# Power_Distro_PCB.net
KiCad netlist of a schematic drawn in EAGLE
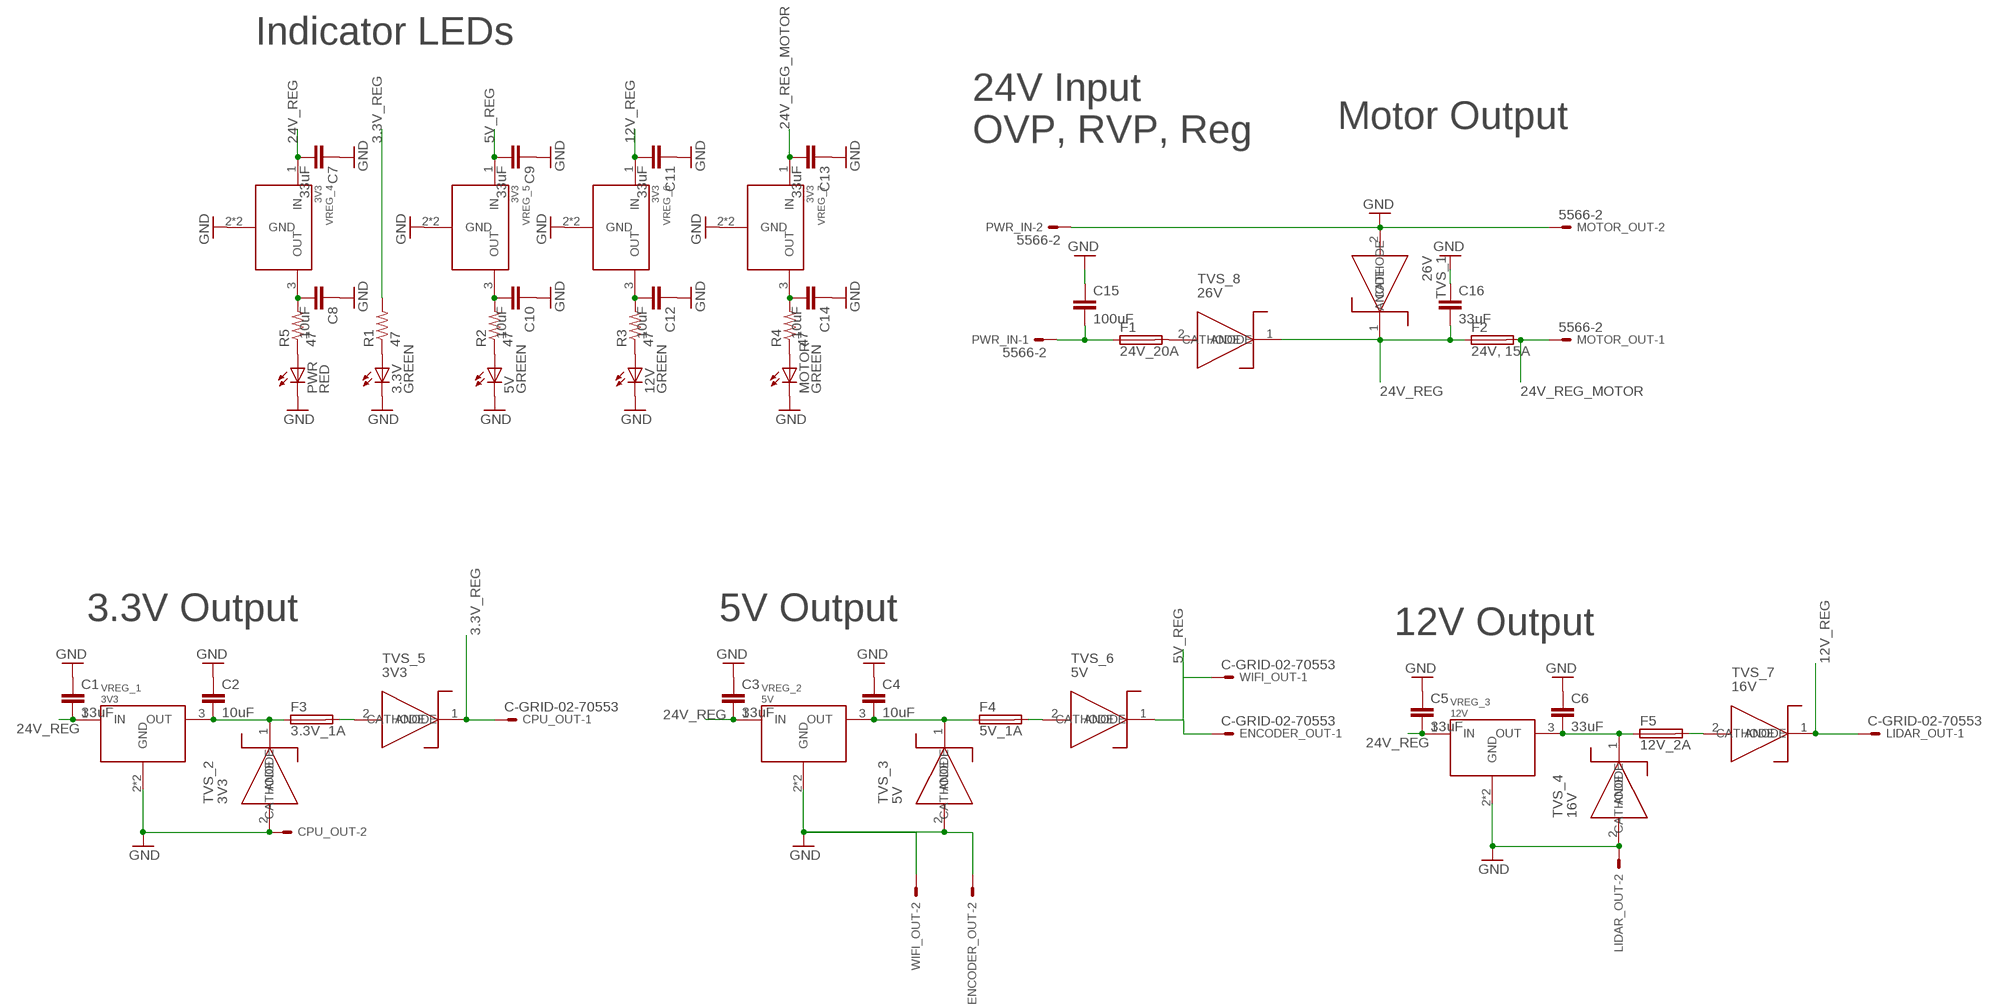
[diagram p0: schematic, sheet 1]

(export (version "E")
  (design (tool "Eeschema 10.0.6"))
  (components
    (comp (ref "3.3V")
      (value "GREEN")
      (footprint "eagle-import:SML1206")
      (libsource (lib "eagle-import") (part "LEDSML1206"))
    )
    (comp (ref "5V")
      (value "GREEN")
      (footprint "eagle-import:SML1206")
      (libsource (lib "eagle-import") (part "LEDSML1206"))
    )
    (comp (ref "12V")
      (value "GREEN")
      (footprint "eagle-import:SML1206")
      (libsource (lib "eagle-import") (part "LEDSML1206"))
    )
    (comp (ref "C1")
      (value "33uF")
      (footprint "eagle-import:C1206")
      (libsource (lib "eagle-import") (part "C-EUC1206"))
    )
    (comp (ref "C2")
      (value "10uF")
      (footprint "eagle-import:C1206")
      (libsource (lib "eagle-import") (part "C-EUC1206"))
    )
    (comp (ref "C3")
      (value "33uF")
      (footprint "eagle-import:C1206")
      (libsource (lib "eagle-import") (part "C-EUC1206"))
    )
    (comp (ref "C4")
      (value "10uF")
      (footprint "eagle-import:C1206")
      (libsource (lib "eagle-import") (part "C-EUC1206"))
    )
    (comp (ref "C5")
      (value "33uF")
      (footprint "eagle-import:C1206")
      (libsource (lib "eagle-import") (part "C-EUC1206"))
    )
    (comp (ref "C6")
      (value "33uF")
      (footprint "eagle-import:C1206")
      (libsource (lib "eagle-import") (part "C-EUC1206"))
    )
    (comp (ref "C7")
      (value "33uF")
      (footprint "eagle-import:C1206")
      (libsource (lib "eagle-import") (part "C-EUC1206"))
    )
    (comp (ref "C8")
      (value "10uF")
      (footprint "eagle-import:C1206")
      (libsource (lib "eagle-import") (part "C-EUC1206"))
    )
    (comp (ref "C9")
      (value "33uF")
      (footprint "eagle-import:C1206")
      (libsource (lib "eagle-import") (part "C-EUC1206"))
    )
    (comp (ref "C10")
      (value "10uF")
      (footprint "eagle-import:C1206")
      (libsource (lib "eagle-import") (part "C-EUC1206"))
    )
    (comp (ref "C11")
      (value "33uF")
      (footprint "eagle-import:C1206")
      (libsource (lib "eagle-import") (part "C-EUC1206"))
    )
    (comp (ref "C12")
      (value "10uF")
      (footprint "eagle-import:C1206")
      (libsource (lib "eagle-import") (part "C-EUC1206"))
    )
    (comp (ref "C13")
      (value "33uF")
      (footprint "eagle-import:C1206")
      (libsource (lib "eagle-import") (part "C-EUC1206"))
    )
    (comp (ref "C14")
      (value "10uF")
      (footprint "eagle-import:C1206")
      (libsource (lib "eagle-import") (part "C-EUC1206"))
    )
    (comp (ref "C15")
      (value "100uF")
      (footprint "eagle-import:C1206")
      (libsource (lib "eagle-import") (part "C-EUC1206"))
    )
    (comp (ref "C16")
      (value "33uF")
      (footprint "eagle-import:C1206")
      (libsource (lib "eagle-import") (part "C-EUC1206"))
    )
    (comp (ref "CPU_OUT")
      (value "C-GRID-02-70553")
      (footprint "eagle-import:70553-02")
      (libsource (lib "eagle-import") (part "C-GRID-02-70553"))
    )
    (comp (ref "ENCODER_OUT")
      (value "C-GRID-02-70553")
      (footprint "eagle-import:70553-02")
      (libsource (lib "eagle-import") (part "C-GRID-02-70553"))
    )
    (comp (ref "F1")
      (value "24V_20A")
      (footprint "eagle-import:TE5")
      (libsource (lib "eagle-import") (part "TE5"))
    )
    (comp (ref "F2")
      (value "24V, 15A")
      (footprint "eagle-import:TE5")
      (libsource (lib "eagle-import") (part "TE5"))
    )
    (comp (ref "F3")
      (value "3.3V_1A")
      (footprint "eagle-import:TE5")
      (libsource (lib "eagle-import") (part "TE5"))
    )
    (comp (ref "F4")
      (value "5V_1A")
      (footprint "eagle-import:TE5")
      (libsource (lib "eagle-import") (part "TE5"))
    )
    (comp (ref "F5")
      (value "12V_2A")
      (footprint "eagle-import:TE5")
      (libsource (lib "eagle-import") (part "TE5"))
    )
    (comp (ref "LIDAR_OUT")
      (value "C-GRID-02-70553")
      (footprint "eagle-import:70553-02")
      (libsource (lib "eagle-import") (part "C-GRID-02-70553"))
    )
    (comp (ref "MOTOR")
      (value "GREEN")
      (footprint "eagle-import:SML1206")
      (libsource (lib "eagle-import") (part "LEDSML1206"))
    )
    (comp (ref "MOTOR_OUT")
      (value "5566-2")
      (footprint "eagle-import:5566-2")
      (libsource (lib "eagle-import") (part "5566-2"))
    )
    (comp (ref "PWR")
      (value "RED")
      (footprint "eagle-import:SML1206")
      (libsource (lib "eagle-import") (part "LEDSML1206"))
    )
    (comp (ref "PWR_IN")
      (value "5566-2")
      (footprint "eagle-import:5566-2")
      (libsource (lib "eagle-import") (part "5566-2"))
    )
    (comp (ref "R1")
      (value "47")
      (footprint "eagle-import:R1206")
      (libsource (lib "eagle-import") (part "R-US_R1206"))
    )
    (comp (ref "R2")
      (value "47")
      (footprint "eagle-import:R1206")
      (libsource (lib "eagle-import") (part "R-US_R1206"))
    )
    (comp (ref "R3")
      (value "47")
      (footprint "eagle-import:R1206")
      (libsource (lib "eagle-import") (part "R-US_R1206"))
    )
    (comp (ref "R4")
      (value "47")
      (footprint "eagle-import:R1206")
      (libsource (lib "eagle-import") (part "R-US_R1206"))
    )
    (comp (ref "R5")
      (value "47")
      (footprint "eagle-import:R1206")
      (libsource (lib "eagle-import") (part "R-US_R1206"))
    )
    (comp (ref "TVS_1")
      (value "26V")
      (footprint "eagle-import:DO-214AC")
      (libsource (lib "eagle-import") (part "SMAJ26A_TVSSMA"))
    )
    (comp (ref "TVS_2")
      (value "3V3")
      (footprint "eagle-import:DO-214AA")
      (libsource (lib "eagle-import") (part "SMBJ3V3_TVSSMB"))
    )
    (comp (ref "TVS_3")
      (value "5V")
      (footprint "eagle-import:DO-214AC")
      (libsource (lib "eagle-import") (part "SMAJ5.0_TVSSMA"))
    )
    (comp (ref "TVS_4")
      (value "16V")
      (footprint "eagle-import:DO-214AC")
      (libsource (lib "eagle-import") (part "PRSMA16_TVS"))
    )
    (comp (ref "TVS_5")
      (value "3V3")
      (footprint "eagle-import:DO-214AA")
      (libsource (lib "eagle-import") (part "SMBJ3V3_TVSSMB"))
    )
    (comp (ref "TVS_6")
      (value "5V")
      (footprint "eagle-import:DO-214AC")
      (libsource (lib "eagle-import") (part "SMAJ5.0_TVSSMA"))
    )
    (comp (ref "TVS_7")
      (value "16V")
      (footprint "eagle-import:DO-214AC")
      (libsource (lib "eagle-import") (part "PRSMA16_TVS"))
    )
    (comp (ref "TVS_8")
      (value "26V")
      (footprint "eagle-import:DO-214AC")
      (libsource (lib "eagle-import") (part "SMAJ26A_TVSSMA"))
    )
    (comp (ref "VREG_1")
      (value "3V3")
      (footprint "eagle-import:TO-263-3")
      (libsource (lib "eagle-import") (part "HIGH-CURRENT_REGSMA"))
    )
    (comp (ref "VREG_2")
      (value "5V")
      (footprint "eagle-import:TO-263-3")
      (libsource (lib "eagle-import") (part "HIGH-CURRENT_REGSMA"))
    )
    (comp (ref "VREG_3")
      (value "12V")
      (footprint "eagle-import:TO-263-3")
      (libsource (lib "eagle-import") (part "HIGH-CURRENT_REGSMA"))
    )
    (comp (ref "VREG_4")
      (value "3V3")
      (footprint "eagle-import:TO-263-3")
      (libsource (lib "eagle-import") (part "HIGH-CURRENT_REGSMA"))
    )
    (comp (ref "VREG_5")
      (value "3V3")
      (footprint "eagle-import:TO-263-3")
      (libsource (lib "eagle-import") (part "HIGH-CURRENT_REGSMA"))
    )
    (comp (ref "VREG_6")
      (value "3V3")
      (footprint "eagle-import:TO-263-3")
      (libsource (lib "eagle-import") (part "HIGH-CURRENT_REGSMA"))
    )
    (comp (ref "VREG_7")
      (value "3V3")
      (footprint "eagle-import:TO-263-3")
      (libsource (lib "eagle-import") (part "HIGH-CURRENT_REGSMA"))
    )
    (comp (ref "WIFI_OUT")
      (value "C-GRID-02-70553")
      (footprint "eagle-import:70553-02")
      (libsource (lib "eagle-import") (part "C-GRID-02-70553"))
    )
  )
  (nets
    (net (code "1") (name "/3.3V_REG") (class "Default")
      (node (ref "CPU_OUT") (pin "1") (pinfunction "S_1") (pintype "passive"))
      (node (ref "R1") (pin "2") (pinfunction "2_2") (pintype "passive"))
      (node (ref "TVS_5") (pin "1") (pinfunction "CATHODE_1") (pintype "bidirectional"))
    )
    (net (code "2") (name "/5V_REG") (class "Default")
      (node (ref "C9") (pin "2") (pinfunction "2_2") (pintype "passive"))
      (node (ref "ENCODER_OUT") (pin "1") (pinfunction "S_1") (pintype "passive"))
      (node (ref "TVS_6") (pin "1") (pinfunction "CATHODE_1") (pintype "bidirectional"))
      (node (ref "VREG_5") (pin "1") (pinfunction "IN_1") (pintype "bidirectional"))
      (node (ref "WIFI_OUT") (pin "1") (pinfunction "S_1") (pintype "passive"))
    )
    (net (code "3") (name "/12V_REG") (class "Default")
      (node (ref "C11") (pin "2") (pinfunction "2_2") (pintype "passive"))
      (node (ref "LIDAR_OUT") (pin "1") (pinfunction "S_1") (pintype "passive"))
      (node (ref "TVS_7") (pin "1") (pinfunction "CATHODE_1") (pintype "bidirectional"))
      (node (ref "VREG_6") (pin "1") (pinfunction "IN_1") (pintype "bidirectional"))
    )
    (net (code "4") (name "/24V_REG") (class "Default")
      (node (ref "C1") (pin "2") (pinfunction "2_2") (pintype "passive"))
      (node (ref "C16") (pin "2") (pinfunction "2_2") (pintype "passive"))
      (node (ref "C3") (pin "2") (pinfunction "2_2") (pintype "passive"))
      (node (ref "C5") (pin "2") (pinfunction "2_2") (pintype "passive"))
      (node (ref "C7") (pin "2") (pinfunction "2_2") (pintype "passive"))
      (node (ref "F2") (pin "1") (pinfunction "1_1") (pintype "passive"))
      (node (ref "TVS_1") (pin "1") (pinfunction "CATHODE_1") (pintype "bidirectional"))
      (node (ref "TVS_8") (pin "1") (pinfunction "CATHODE_1") (pintype "bidirectional"))
      (node (ref "VREG_1") (pin "1") (pinfunction "IN_1") (pintype "bidirectional"))
      (node (ref "VREG_2") (pin "1") (pinfunction "IN_1") (pintype "bidirectional"))
      (node (ref "VREG_3") (pin "1") (pinfunction "IN_1") (pintype "bidirectional"))
      (node (ref "VREG_4") (pin "1") (pinfunction "IN_1") (pintype "bidirectional"))
    )
    (net (code "5") (name "/24V_REG_MOTOR") (class "Default")
      (node (ref "C13") (pin "2") (pinfunction "2_2") (pintype "passive"))
      (node (ref "F2") (pin "2") (pinfunction "2_2") (pintype "passive"))
      (node (ref "MOTOR_OUT") (pin "1") (pinfunction "S_1") (pintype "passive"))
      (node (ref "VREG_7") (pin "1") (pinfunction "IN_1") (pintype "bidirectional"))
    )
    (net (code "6") (name "GND") (class "Default")
      (node (ref "12V") (pin "C") (pinfunction "C_C") (pintype "passive"))
      (node (ref "3.3V") (pin "C") (pinfunction "C_C") (pintype "passive"))
      (node (ref "5V") (pin "C") (pinfunction "C_C") (pintype "passive"))
      (node (ref "C1") (pin "1") (pinfunction "1_1") (pintype "passive"))
      (node (ref "C10") (pin "1") (pinfunction "1_1") (pintype "passive"))
      (node (ref "C11") (pin "1") (pinfunction "1_1") (pintype "passive"))
      (node (ref "C12") (pin "1") (pinfunction "1_1") (pintype "passive"))
      (node (ref "C13") (pin "1") (pinfunction "1_1") (pintype "passive"))
      (node (ref "C14") (pin "1") (pinfunction "1_1") (pintype "passive"))
      (node (ref "C15") (pin "1") (pinfunction "1_1") (pintype "passive"))
      (node (ref "C16") (pin "1") (pinfunction "1_1") (pintype "passive"))
      (node (ref "C2") (pin "1") (pinfunction "1_1") (pintype "passive"))
      (node (ref "C3") (pin "1") (pinfunction "1_1") (pintype "passive"))
      (node (ref "C4") (pin "1") (pinfunction "1_1") (pintype "passive"))
      (node (ref "C5") (pin "1") (pinfunction "1_1") (pintype "passive"))
      (node (ref "C6") (pin "1") (pinfunction "1_1") (pintype "passive"))
      (node (ref "C7") (pin "1") (pinfunction "1_1") (pintype "passive"))
      (node (ref "C8") (pin "1") (pinfunction "1_1") (pintype "passive"))
      (node (ref "C9") (pin "1") (pinfunction "1_1") (pintype "passive"))
      (node (ref "CPU_OUT") (pin "2") (pinfunction "S_2") (pintype "passive"))
      (node (ref "ENCODER_OUT") (pin "2") (pinfunction "S_2") (pintype "passive"))
      (node (ref "LIDAR_OUT") (pin "2") (pinfunction "S_2") (pintype "passive"))
      (node (ref "MOTOR") (pin "C") (pinfunction "C_C") (pintype "passive"))
      (node (ref "MOTOR_OUT") (pin "2") (pinfunction "S_2") (pintype "passive"))
      (node (ref "PWR") (pin "C") (pinfunction "C_C") (pintype "passive"))
      (node (ref "PWR_IN") (pin "2") (pinfunction "S_2") (pintype "passive"))
      (node (ref "TVS_1") (pin "2") (pinfunction "ANODE_2") (pintype "bidirectional"))
      (node (ref "TVS_2") (pin "2") (pinfunction "ANODE_2") (pintype "bidirectional"))
      (node (ref "TVS_3") (pin "2") (pinfunction "ANODE_2") (pintype "bidirectional"))
      (node (ref "TVS_4") (pin "2") (pinfunction "ANODE_2") (pintype "bidirectional"))
      (node (ref "VREG_1") (pin "2") (pinfunction "GND_2") (pintype "bidirectional"))
      (node (ref "VREG_1") (pin "4") (pinfunction "GND_4") (pintype "bidirectional"))
      (node (ref "VREG_2") (pin "2") (pinfunction "GND_2") (pintype "bidirectional"))
      (node (ref "VREG_2") (pin "4") (pinfunction "GND_4") (pintype "bidirectional"))
      (node (ref "VREG_3") (pin "2") (pinfunction "GND_2") (pintype "bidirectional"))
      (node (ref "VREG_3") (pin "4") (pinfunction "GND_4") (pintype "bidirectional"))
      (node (ref "VREG_4") (pin "2") (pinfunction "GND_2") (pintype "bidirectional"))
      (node (ref "VREG_4") (pin "4") (pinfunction "GND_4") (pintype "bidirectional"))
      (node (ref "VREG_5") (pin "2") (pinfunction "GND_2") (pintype "bidirectional"))
      (node (ref "VREG_5") (pin "4") (pinfunction "GND_4") (pintype "bidirectional"))
      (node (ref "VREG_6") (pin "2") (pinfunction "GND_2") (pintype "bidirectional"))
      (node (ref "VREG_6") (pin "4") (pinfunction "GND_4") (pintype "bidirectional"))
      (node (ref "VREG_7") (pin "2") (pinfunction "GND_2") (pintype "bidirectional"))
      (node (ref "VREG_7") (pin "4") (pinfunction "GND_4") (pintype "bidirectional"))
      (node (ref "WIFI_OUT") (pin "2") (pinfunction "S_2") (pintype "passive"))
    )
    (net (code "7") (name "Net-(3.3V-PadA)") (class "Default")
      (node (ref "3.3V") (pin "A") (pinfunction "A_A") (pintype "passive"))
      (node (ref "R1") (pin "1") (pinfunction "1_1") (pintype "passive"))
    )
    (net (code "8") (name "Net-(5V-PadA)") (class "Default")
      (node (ref "5V") (pin "A") (pinfunction "A_A") (pintype "passive"))
      (node (ref "R2") (pin "1") (pinfunction "1_1") (pintype "passive"))
    )
    (net (code "9") (name "Net-(12V-PadA)") (class "Default")
      (node (ref "12V") (pin "A") (pinfunction "A_A") (pintype "passive"))
      (node (ref "R3") (pin "1") (pinfunction "1_1") (pintype "passive"))
    )
    (net (code "10") (name "Net-(MOTOR-PadA)") (class "Default")
      (node (ref "MOTOR") (pin "A") (pinfunction "A_A") (pintype "passive"))
      (node (ref "R4") (pin "1") (pinfunction "1_1") (pintype "passive"))
    )
    (net (code "11") (name "Net-(PWR-PadA)") (class "Default")
      (node (ref "PWR") (pin "A") (pinfunction "A_A") (pintype "passive"))
      (node (ref "R5") (pin "1") (pinfunction "1_1") (pintype "passive"))
    )
    (net (code "12") (name "Net-(PWR_INA-S)") (class "Default")
      (node (ref "C15") (pin "2") (pinfunction "2_2") (pintype "passive"))
      (node (ref "F1") (pin "1") (pinfunction "1_1") (pintype "passive"))
      (node (ref "PWR_IN") (pin "1") (pinfunction "S_1") (pintype "passive"))
    )
    (net (code "13") (name "Net-(TVS_2-CATHODE)") (class "Default")
      (node (ref "C2") (pin "2") (pinfunction "2_2") (pintype "passive"))
      (node (ref "F3") (pin "1") (pinfunction "1_1") (pintype "passive"))
      (node (ref "TVS_2") (pin "1") (pinfunction "CATHODE_1") (pintype "bidirectional"))
      (node (ref "VREG_1") (pin "3") (pinfunction "OUT_3") (pintype "bidirectional"))
    )
    (net (code "14") (name "Net-(TVS_3-CATHODE)") (class "Default")
      (node (ref "C4") (pin "2") (pinfunction "2_2") (pintype "passive"))
      (node (ref "F4") (pin "1") (pinfunction "1_1") (pintype "passive"))
      (node (ref "TVS_3") (pin "1") (pinfunction "CATHODE_1") (pintype "bidirectional"))
      (node (ref "VREG_2") (pin "3") (pinfunction "OUT_3") (pintype "bidirectional"))
    )
    (net (code "15") (name "Net-(TVS_4-CATHODE)") (class "Default")
      (node (ref "C6") (pin "2") (pinfunction "2_2") (pintype "passive"))
      (node (ref "F5") (pin "1") (pinfunction "1_1") (pintype "passive"))
      (node (ref "TVS_4") (pin "1") (pinfunction "CATHODE_1") (pintype "bidirectional"))
      (node (ref "VREG_3") (pin "3") (pinfunction "OUT_3") (pintype "bidirectional"))
    )
    (net (code "16") (name "Net-(TVS_5-ANODE)") (class "Default")
      (node (ref "F3") (pin "2") (pinfunction "2_2") (pintype "passive"))
      (node (ref "TVS_5") (pin "2") (pinfunction "ANODE_2") (pintype "bidirectional"))
    )
    (net (code "17") (name "Net-(TVS_6-ANODE)") (class "Default")
      (node (ref "F4") (pin "2") (pinfunction "2_2") (pintype "passive"))
      (node (ref "TVS_6") (pin "2") (pinfunction "ANODE_2") (pintype "bidirectional"))
    )
    (net (code "18") (name "Net-(TVS_7-ANODE)") (class "Default")
      (node (ref "F5") (pin "2") (pinfunction "2_2") (pintype "passive"))
      (node (ref "TVS_7") (pin "2") (pinfunction "ANODE_2") (pintype "bidirectional"))
    )
    (net (code "19") (name "Net-(TVS_8-ANODE)") (class "Default")
      (node (ref "F1") (pin "2") (pinfunction "2_2") (pintype "passive"))
      (node (ref "TVS_8") (pin "2") (pinfunction "ANODE_2") (pintype "bidirectional"))
    )
    (net (code "20") (name "Net-(VREG_4-OUT)") (class "Default")
      (node (ref "C8") (pin "2") (pinfunction "2_2") (pintype "passive"))
      (node (ref "R5") (pin "2") (pinfunction "2_2") (pintype "passive"))
      (node (ref "VREG_4") (pin "3") (pinfunction "OUT_3") (pintype "bidirectional"))
    )
    (net (code "21") (name "Net-(VREG_5-OUT)") (class "Default")
      (node (ref "C10") (pin "2") (pinfunction "2_2") (pintype "passive"))
      (node (ref "R2") (pin "2") (pinfunction "2_2") (pintype "passive"))
      (node (ref "VREG_5") (pin "3") (pinfunction "OUT_3") (pintype "bidirectional"))
    )
    (net (code "22") (name "Net-(VREG_6-OUT)") (class "Default")
      (node (ref "C12") (pin "2") (pinfunction "2_2") (pintype "passive"))
      (node (ref "R3") (pin "2") (pinfunction "2_2") (pintype "passive"))
      (node (ref "VREG_6") (pin "3") (pinfunction "OUT_3") (pintype "bidirectional"))
    )
    (net (code "23") (name "Net-(VREG_7-OUT)") (class "Default")
      (node (ref "C14") (pin "2") (pinfunction "2_2") (pintype "passive"))
      (node (ref "R4") (pin "2") (pinfunction "2_2") (pintype "passive"))
      (node (ref "VREG_7") (pin "3") (pinfunction "OUT_3") (pintype "bidirectional"))
    )
  )
)
